# mainPower.net
KiCad netlist of a schematic drawn in Altium Designer
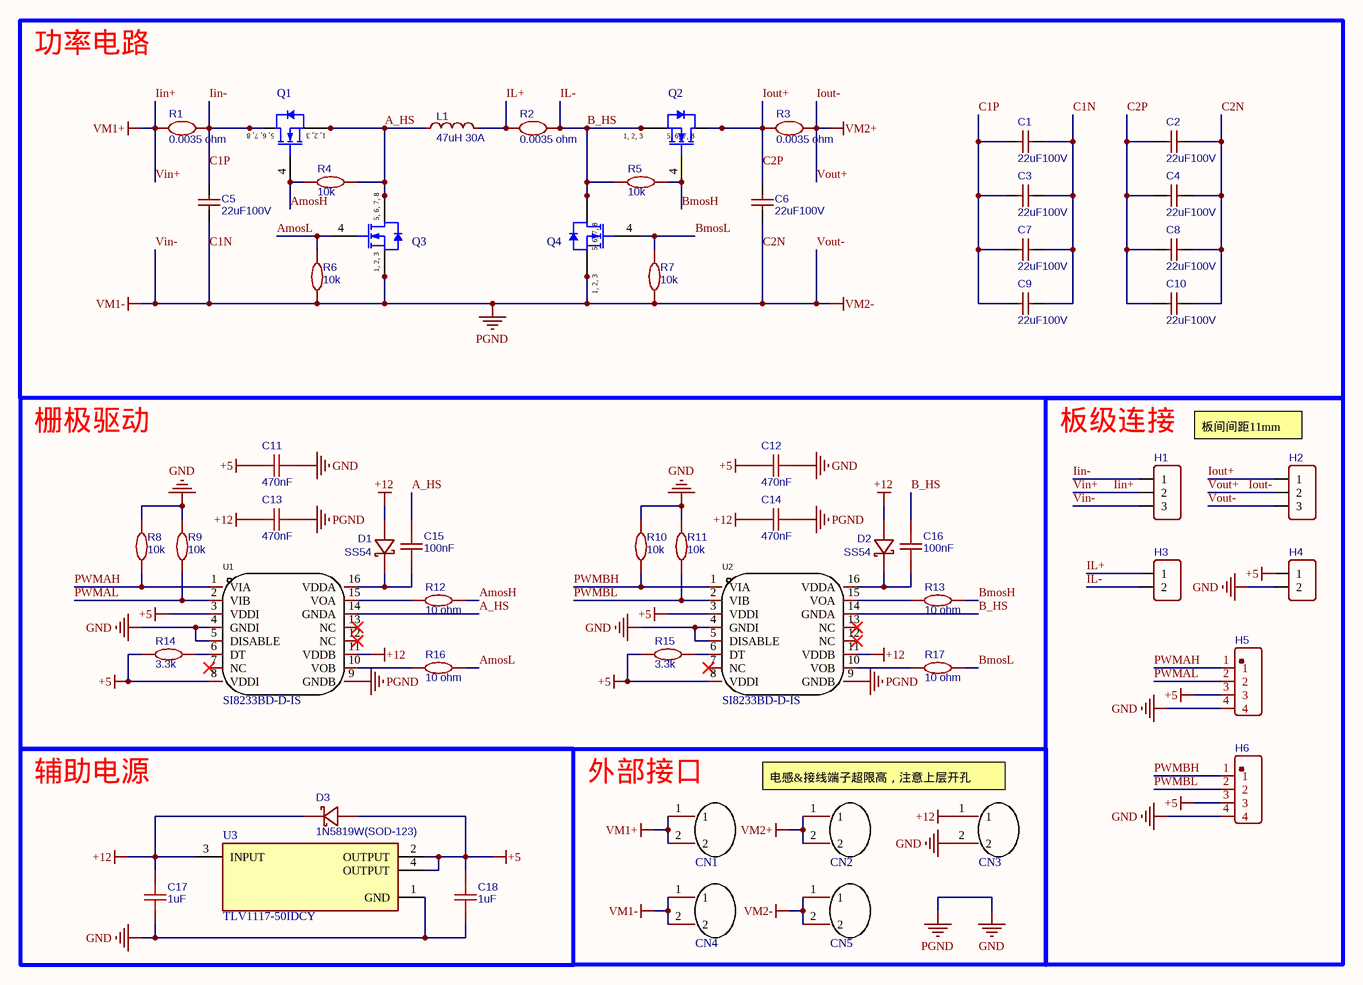
[diagram p0: mainPower.SchDoc]

(export (version "E")
  (design (tool "Eeschema 10.0.6"))
  (components
    (comp (ref "C1")
      (value "22uF100V")
      (footprint "C1206")
      (fields
        (field (name "BOM_MANUFACTURER PART") "1206B102K202NT")
        (field (name "BOM_SUPPLIER PART") "C9196")
      )
      (libsource (lib "RC_schlib") (part "C1206"))
    )
    (comp (ref "C2")
      (value "22uF100V")
      (footprint "C1206")
      (fields
        (field (name "BOM_MANUFACTURER PART") "1206B102K202NT")
        (field (name "BOM_SUPPLIER PART") "C9196")
      )
      (libsource (lib "RC_schlib") (part "C1206"))
    )
    (comp (ref "C3")
      (value "22uF100V")
      (footprint "C1206")
      (fields
        (field (name "BOM_MANUFACTURER PART") "1206B102K202NT")
        (field (name "BOM_SUPPLIER PART") "C9196")
      )
      (libsource (lib "RC_schlib") (part "C1206"))
    )
    (comp (ref "C4")
      (value "22uF100V")
      (footprint "C1206")
      (fields
        (field (name "BOM_MANUFACTURER PART") "1206B102K202NT")
        (field (name "BOM_SUPPLIER PART") "C9196")
      )
      (libsource (lib "RC_schlib") (part "C1206"))
    )
    (comp (ref "C5")
      (value "22uF100V")
      (footprint "C1206")
      (fields
        (field (name "BOM_MANUFACTURER PART") "1206B102K202NT")
        (field (name "BOM_SUPPLIER PART") "C9196")
      )
      (libsource (lib "RC_schlib") (part "C1206"))
    )
    (comp (ref "C6")
      (value "22uF100V")
      (footprint "C1206")
      (fields
        (field (name "BOM_MANUFACTURER PART") "1206B102K202NT")
        (field (name "BOM_SUPPLIER PART") "C9196")
      )
      (libsource (lib "RC_schlib") (part "C1206"))
    )
    (comp (ref "C7")
      (value "22uF100V")
      (footprint "C1206")
      (fields
        (field (name "BOM_MANUFACTURER PART") "1206B102K202NT")
        (field (name "BOM_SUPPLIER PART") "C9196")
      )
      (libsource (lib "RC_schlib") (part "C1206"))
    )
    (comp (ref "C8")
      (value "22uF100V")
      (footprint "C1206")
      (fields
        (field (name "BOM_MANUFACTURER PART") "1206B102K202NT")
        (field (name "BOM_SUPPLIER PART") "C9196")
      )
      (libsource (lib "RC_schlib") (part "C1206"))
    )
    (comp (ref "C9")
      (value "22uF100V")
      (footprint "C1206")
      (fields
        (field (name "BOM_MANUFACTURER PART") "1206B102K202NT")
        (field (name "BOM_SUPPLIER PART") "C9196")
      )
      (libsource (lib "RC_schlib") (part "C1206"))
    )
    (comp (ref "C10")
      (value "22uF100V")
      (footprint "C1206")
      (fields
        (field (name "BOM_MANUFACTURER PART") "1206B102K202NT")
        (field (name "BOM_SUPPLIER PART") "C9196")
      )
      (libsource (lib "RC_schlib") (part "C1206"))
    )
    (comp (ref "C11")
      (value "470nF")
      (footprint "C0603")
      (fields
        (field (name "BOM_MANUFACTURER PART") "CC0603KRX7R9BB104")
        (field (name "BOM_SUPPLIER PART") "C14663")
      )
      (libsource (lib "RC_schlib") (part "C0603"))
    )
    (comp (ref "C12")
      (value "470nF")
      (footprint "C0603")
      (fields
        (field (name "BOM_MANUFACTURER PART") "CC0603KRX7R9BB104")
        (field (name "BOM_SUPPLIER PART") "C14663")
      )
      (libsource (lib "RC_schlib") (part "C0603"))
    )
    (comp (ref "C13")
      (value "470nF")
      (footprint "C0603")
      (fields
        (field (name "BOM_MANUFACTURER PART") "CC0603KRX7R9BB104")
        (field (name "BOM_SUPPLIER PART") "C14663")
      )
      (libsource (lib "RC_schlib") (part "C0603"))
    )
    (comp (ref "C14")
      (value "470nF")
      (footprint "C0603")
      (fields
        (field (name "BOM_MANUFACTURER PART") "CC0603KRX7R9BB104")
        (field (name "BOM_SUPPLIER PART") "C14663")
      )
      (libsource (lib "RC_schlib") (part "C0603"))
    )
    (comp (ref "C15")
      (value "100nF")
      (footprint "C0603")
      (fields
        (field (name "BOM_MANUFACTURER PART") "CC0603KRX7R9BB104")
        (field (name "BOM_SUPPLIER PART") "C14663")
      )
      (libsource (lib "RC_schlib") (part "C0603"))
    )
    (comp (ref "C16")
      (value "100nF")
      (footprint "C0603")
      (fields
        (field (name "BOM_MANUFACTURER PART") "CC0603KRX7R9BB104")
        (field (name "BOM_SUPPLIER PART") "C14663")
      )
      (libsource (lib "RC_schlib") (part "C0603"))
    )
    (comp (ref "C17")
      (value "1uF")
      (footprint "C0603")
      (fields
        (field (name "BOM_MANUFACTURER PART") "CC0603KRX7R9BB104")
        (field (name "BOM_SUPPLIER PART") "C14663")
      )
      (libsource (lib "RC_schlib") (part "C0603"))
    )
    (comp (ref "C18")
      (value "1uF")
      (footprint "C0603")
      (fields
        (field (name "BOM_MANUFACTURER PART") "CC0603KRX7R9BB104")
        (field (name "BOM_SUPPLIER PART") "C14663")
      )
      (libsource (lib "RC_schlib") (part "C0603"))
    )
    (comp (ref "CN1")
      (value "1729128")
      (footprint "CONN-TH_2P-P5.08")
      (description "间距:5.08mm;排数:1;每排PIN数:2;安装方式:直针;额定电流:13.5A;额定电压:400V;工作温度范围:-;颜色:绿色;")
      (fields (field (name "MANUFACTURER") "Phoenix Contact(菲尼克斯)"))
      (libsource (lib "MKDSN") (part "MKDSN5.08-2P"))
    )
    (comp (ref "CN2")
      (value "1729128")
      (footprint "CONN-TH_2P-P5.08")
      (description "间距:5.08mm;排数:1;每排PIN数:2;安装方式:直针;额定电流:13.5A;额定电压:400V;工作温度范围:-;颜色:绿色;")
      (fields (field (name "MANUFACTURER") "Phoenix Contact(菲尼克斯)"))
      (libsource (lib "MKDSN") (part "MKDSN5.08-2P"))
    )
    (comp (ref "CN3")
      (value "1729128")
      (footprint "CONN-TH_2P-P5.08")
      (description "间距:5.08mm;排数:1;每排PIN数:2;安装方式:直针;额定电流:13.5A;额定电压:400V;工作温度范围:-;颜色:绿色;")
      (fields (field (name "MANUFACTURER") "Phoenix Contact(菲尼克斯)"))
      (libsource (lib "MKDSN") (part "MKDSN5.08-2P"))
    )
    (comp (ref "CN4")
      (value "1729128")
      (footprint "CONN-TH_2P-P5.08")
      (description "间距:5.08mm;排数:1;每排PIN数:2;安装方式:直针;额定电流:13.5A;额定电压:400V;工作温度范围:-;颜色:绿色;")
      (fields (field (name "MANUFACTURER") "Phoenix Contact(菲尼克斯)"))
      (libsource (lib "MKDSN") (part "MKDSN5.08-2P"))
    )
    (comp (ref "CN5")
      (value "1729128")
      (footprint "CONN-TH_2P-P5.08")
      (description "间距:5.08mm;排数:1;每排PIN数:2;安装方式:直针;额定电流:13.5A;额定电压:400V;工作温度范围:-;颜色:绿色;")
      (fields (field (name "MANUFACTURER") "Phoenix Contact(菲尼克斯)"))
      (libsource (lib "MKDSN") (part "MKDSN5.08-2P"))
    )
    (comp (ref "D1")
      (value "SS54")
      (footprint "SMA")
      (fields
        (field (name "BOM_SUPPLIER PART") "C2931787")
        (field (name "BOM_MANUFACTURER PART") "SS34")
        (field (name "CONTRIBUTOR") "LCSC")
      )
      (libsource (lib "Diode_schlib") (part "SS34(SMA)"))
    )
    (comp (ref "D2")
      (value "SS54")
      (footprint "SMA")
      (fields
        (field (name "BOM_SUPPLIER PART") "C2931787")
        (field (name "BOM_MANUFACTURER PART") "SS34")
        (field (name "CONTRIBUTOR") "LCSC")
      )
      (libsource (lib "Diode_schlib") (part "SS34(SMA)"))
    )
    (comp (ref "D3")
      (value "1N5819W(SOD-123)")
      (footprint "SOD-123")
      (fields
        (field (name "BOM_SUPPLIER PART") "C2931787")
        (field (name "BOM_MANUFACTURER PART") "SS34")
        (field (name "CONTRIBUTOR") "LCSC")
      )
      (libsource (lib "Diode_schlib") (part "1N5819W(SOD-123)"))
    )
    (comp (ref "H1")
      (value "Header-Male-2.54_1x3")
      (footprint "HDR2.54-LI-3P")
      (fields
        (field (name "BOM_MANUFACTURER PART") "Header2.54mm 1*3P")
        (field (name "BOM_SUPPLIER PART") "C49257")
      )
      (libsource (lib "2.54CN_schlib") (part "Header-Male-2.54_1x3"))
    )
    (comp (ref "H2")
      (value "Header-Male-2.54_1x3")
      (footprint "HDR2.54-LI-3P")
      (fields
        (field (name "BOM_MANUFACTURER PART") "Header2.54mm 1*3P")
        (field (name "BOM_SUPPLIER PART") "C49257")
      )
      (libsource (lib "2.54CN_schlib") (part "Header-Male-2.54_1x3"))
    )
    (comp (ref "H3")
      (value "Header-Male-2.54_1x2")
      (footprint "HDR2.54-LI-2P")
      (fields
        (field (name "BOM_MANUFACTURER PART") "Header2.54mm 1*3P")
        (field (name "BOM_SUPPLIER PART") "C49257")
      )
      (libsource (lib "2.54CN_schlib") (part "Header-Male-2.54_1x2"))
    )
    (comp (ref "H4")
      (value "Header-Male-2.54_1x2")
      (footprint "HDR2.54-LI-2P")
      (fields
        (field (name "BOM_MANUFACTURER PART") "Header2.54mm 1*3P")
        (field (name "BOM_SUPPLIER PART") "C49257")
      )
      (libsource (lib "2.54CN_schlib") (part "Header-Male-2.54_1x2"))
    )
    (comp (ref "H5")
      (value "Header-Male-2.54_1x4")
      (footprint "HDR2.54-LI-4P")
      (fields (field (name "BOM_SUPPLIER PART") "C247921") (field (name "CONTRIBUTOR") "LCSC"))
      (libsource (lib "2.54CN_schlib") (part "Header-Male-2.54_1x4"))
    )
    (comp (ref "H6")
      (value "Header-Male-2.54_1x4")
      (footprint "HDR2.54-LI-4P")
      (fields (field (name "BOM_SUPPLIER PART") "C247921") (field (name "CONTRIBUTOR") "LCSC"))
      (libsource (lib "2.54CN_schlib") (part "Header-Male-2.54_1x4"))
    )
    (comp (ref "L1")
      (value "47uH 30A")
      (footprint "106-125立式")
      (fields
        (field (name "BOM_SUPPLIER PART") "C2936653")
        (field (name "BOM_MANUFACTURER PART") "HA42-4R7MT")
        (field (name "CONTRIBUTOR") "LCSC")
      )
      (libsource (lib "Inductance_schlib") (part "106-125铁硅铝磁环电感"))
    )
    (comp (ref "Q1")
      (value "BSC070N10NS3 G")
      (footprint "INF-PG-TDSON-8-1_V")
      (fields
        (field (name "MANUFACTURER") "Infineon")
        (field (name "MANUFACTURER PART NUMBER") "BSC070N10NS3G")
      )
      (libsource (lib "MOSFET_schlib") (part "BSC070N10NS3G"))
    )
    (comp (ref "Q2")
      (value "BSC070N10NS3 G")
      (footprint "INF-PG-TDSON-8-1_V")
      (fields
        (field (name "MANUFACTURER") "Infineon")
        (field (name "MANUFACTURER PART NUMBER") "BSC070N10NS3G")
      )
      (libsource (lib "MOSFET_schlib") (part "BSC070N10NS3G"))
    )
    (comp (ref "Q3")
      (value "BSC070N10NS3 G")
      (footprint "INF-PG-TDSON-8-1_V")
      (fields
        (field (name "MANUFACTURER") "Infineon")
        (field (name "MANUFACTURER PART NUMBER") "BSC070N10NS3G")
      )
      (libsource (lib "MOSFET_schlib") (part "BSC070N10NS3G"))
    )
    (comp (ref "Q4")
      (value "BSC070N10NS3 G")
      (footprint "INF-PG-TDSON-8-1_V")
      (fields
        (field (name "MANUFACTURER") "Infineon")
        (field (name "MANUFACTURER PART NUMBER") "BSC070N10NS3G")
      )
      (libsource (lib "MOSFET_schlib") (part "BSC070N10NS3G"))
    )
    (comp (ref "R1")
      (value "0.0035 ohm")
      (footprint "R2512")
      (fields
        (field (name "BOM_SUPPLIER PART") "C375694")
        (field (name "BOM_MANUFACTURER PART") "SR2512FK-0751RL")
        (field (name "CONTRIBUTOR") "LCSC")
      )
      (libsource (lib "RC_schlib") (part "R2512"))
    )
    (comp (ref "R2")
      (value "0.0035 ohm")
      (footprint "R2512")
      (fields
        (field (name "BOM_SUPPLIER PART") "C375694")
        (field (name "BOM_MANUFACTURER PART") "SR2512FK-0751RL")
        (field (name "CONTRIBUTOR") "LCSC")
      )
      (libsource (lib "RC_schlib") (part "R2512"))
    )
    (comp (ref "R3")
      (value "0.0035 ohm")
      (footprint "R2512")
      (fields
        (field (name "BOM_SUPPLIER PART") "C375694")
        (field (name "BOM_MANUFACTURER PART") "SR2512FK-0751RL")
        (field (name "CONTRIBUTOR") "LCSC")
      )
      (libsource (lib "RC_schlib") (part "R2512"))
    )
    (comp (ref "R4")
      (value "10k")
      (footprint "R0603")
      (fields
        (field (name "BOM_SUPPLIER PART") "C326890")
        (field (name "BOM_MANUFACTURER PART") "SR0603JR-071RL")
        (field (name "CONTRIBUTOR") "LCSC")
      )
      (libsource (lib "RC_schlib") (part "R0603"))
    )
    (comp (ref "R5")
      (value "10k")
      (footprint "R0603")
      (fields
        (field (name "BOM_SUPPLIER PART") "C326890")
        (field (name "BOM_MANUFACTURER PART") "SR0603JR-071RL")
        (field (name "CONTRIBUTOR") "LCSC")
      )
      (libsource (lib "RC_schlib") (part "R0603"))
    )
    (comp (ref "R6")
      (value "10k")
      (footprint "R0603")
      (fields
        (field (name "BOM_SUPPLIER PART") "C326890")
        (field (name "BOM_MANUFACTURER PART") "SR0603JR-071RL")
        (field (name "CONTRIBUTOR") "LCSC")
      )
      (libsource (lib "RC_schlib") (part "R0603"))
    )
    (comp (ref "R7")
      (value "10k")
      (footprint "R0603")
      (fields
        (field (name "BOM_SUPPLIER PART") "C326890")
        (field (name "BOM_MANUFACTURER PART") "SR0603JR-071RL")
        (field (name "CONTRIBUTOR") "LCSC")
      )
      (libsource (lib "RC_schlib") (part "R0603"))
    )
    (comp (ref "R8")
      (value "10k")
      (footprint "R0603")
      (fields
        (field (name "BOM_SUPPLIER PART") "C326890")
        (field (name "BOM_MANUFACTURER PART") "SR0603JR-071RL")
        (field (name "CONTRIBUTOR") "LCSC")
      )
      (libsource (lib "RC_schlib") (part "R0603"))
    )
    (comp (ref "R9")
      (value "10k")
      (footprint "R0603")
      (fields
        (field (name "BOM_SUPPLIER PART") "C326890")
        (field (name "BOM_MANUFACTURER PART") "SR0603JR-071RL")
        (field (name "CONTRIBUTOR") "LCSC")
      )
      (libsource (lib "RC_schlib") (part "R0603"))
    )
    (comp (ref "R10")
      (value "10k")
      (footprint "R0603")
      (fields
        (field (name "BOM_SUPPLIER PART") "C326890")
        (field (name "BOM_MANUFACTURER PART") "SR0603JR-071RL")
        (field (name "CONTRIBUTOR") "LCSC")
      )
      (libsource (lib "RC_schlib") (part "R0603"))
    )
    (comp (ref "R11")
      (value "10k")
      (footprint "R0603")
      (fields
        (field (name "BOM_SUPPLIER PART") "C326890")
        (field (name "BOM_MANUFACTURER PART") "SR0603JR-071RL")
        (field (name "CONTRIBUTOR") "LCSC")
      )
      (libsource (lib "RC_schlib") (part "R0603"))
    )
    (comp (ref "R12")
      (value "10 ohm")
      (footprint "R0603")
      (fields
        (field (name "BOM_SUPPLIER PART") "C326890")
        (field (name "BOM_MANUFACTURER PART") "SR0603JR-071RL")
        (field (name "CONTRIBUTOR") "LCSC")
      )
      (libsource (lib "RC_schlib") (part "R0603"))
    )
    (comp (ref "R13")
      (value "10 ohm")
      (footprint "R0603")
      (fields
        (field (name "BOM_SUPPLIER PART") "C326890")
        (field (name "BOM_MANUFACTURER PART") "SR0603JR-071RL")
        (field (name "CONTRIBUTOR") "LCSC")
      )
      (libsource (lib "RC_schlib") (part "R0603"))
    )
    (comp (ref "R14")
      (value "3.3k")
      (footprint "R0603")
      (fields
        (field (name "BOM_SUPPLIER PART") "C326890")
        (field (name "BOM_MANUFACTURER PART") "SR0603JR-071RL")
        (field (name "CONTRIBUTOR") "LCSC")
      )
      (libsource (lib "RC_schlib") (part "R0603"))
    )
    (comp (ref "R15")
      (value "3.3k")
      (footprint "R0603")
      (fields
        (field (name "BOM_SUPPLIER PART") "C326890")
        (field (name "BOM_MANUFACTURER PART") "SR0603JR-071RL")
        (field (name "CONTRIBUTOR") "LCSC")
      )
      (libsource (lib "RC_schlib") (part "R0603"))
    )
    (comp (ref "R16")
      (value "10 ohm")
      (footprint "R0603")
      (fields
        (field (name "BOM_SUPPLIER PART") "C326890")
        (field (name "BOM_MANUFACTURER PART") "SR0603JR-071RL")
        (field (name "CONTRIBUTOR") "LCSC")
      )
      (libsource (lib "RC_schlib") (part "R0603"))
    )
    (comp (ref "R17")
      (value "10 ohm")
      (footprint "R0603")
      (fields
        (field (name "BOM_SUPPLIER PART") "C326890")
        (field (name "BOM_MANUFACTURER PART") "SR0603JR-071RL")
        (field (name "CONTRIBUTOR") "LCSC")
      )
      (libsource (lib "RC_schlib") (part "R0603"))
    )
    (comp (ref "U1")
      (value "SI8233BD-D-IS")
      (footprint "SOIC-16_L10.3-W7.5-P1.27-LS10.3-BL")
      (description "高速隔离半桥栅极驱动器")
      (fields (field (name "MANUFACTURER") "SILICON LABS(芯科)"))
      (libsource (lib "IC_schlib") (part "SI8233BD-D-IS"))
    )
    (comp (ref "U2")
      (value "SI8233BD-D-IS")
      (footprint "SOIC-16_L10.3-W7.5-P1.27-LS10.3-BL")
      (description "高速隔离半桥栅极驱动器")
      (fields (field (name "MANUFACTURER") "SILICON LABS(芯科)"))
      (libsource (lib "IC_schlib") (part "SI8233BD-D-IS"))
    )
    (comp (ref "U3")
      (value "TLV1117-50IDCY")
      (footprint "FP-DCY0004A-MFG")
      (description "IC REG LINEAR 5V 800MA SOT223-4")
      (libsource (lib "Altium Content Vault") (part "e308c0431133a401381f8e374ae96fd"))
    )
  )
  (nets
    (net (code "1") (name "+5") (class "Default")
      (node (ref "C11") (pin "2") (pinfunction "2_2") (pintype "passive"))
      (node (ref "C12") (pin "2") (pinfunction "2_2") (pintype "passive"))
      (node (ref "C18") (pin "2") (pinfunction "2_2") (pintype "passive"))
      (node (ref "D3") (pin "1") (pinfunction "A_1") (pintype "passive"))
      (node (ref "H4") (pin "1") (pinfunction "1_1") (pintype "passive"))
      (node (ref "H5") (pin "3") (pinfunction "3_3") (pintype "passive"))
      (node (ref "H6") (pin "3") (pinfunction "3_3") (pintype "passive"))
      (node (ref "R14") (pin "1") (pinfunction "1_1") (pintype "passive"))
      (node (ref "R15") (pin "1") (pinfunction "1_1") (pintype "passive"))
      (node (ref "U1") (pin "3") (pinfunction "VDDI_3") (pintype "passive"))
      (node (ref "U1") (pin "8") (pinfunction "VDDI_8") (pintype "passive"))
      (node (ref "U2") (pin "3") (pinfunction "VDDI_3") (pintype "passive"))
      (node (ref "U2") (pin "8") (pinfunction "VDDI_8") (pintype "passive"))
      (node (ref "U3") (pin "2") (pinfunction "OUTPUT_2") (pintype "power_in"))
      (node (ref "U3") (pin "4") (pinfunction "OUTPUT_4") (pintype "power_in"))
    )
    (net (code "2") (name "+12") (class "Default")
      (node (ref "C13") (pin "2") (pinfunction "2_2") (pintype "passive"))
      (node (ref "C14") (pin "2") (pinfunction "2_2") (pintype "passive"))
      (node (ref "C17") (pin "2") (pinfunction "2_2") (pintype "passive"))
      (node (ref "CN3") (pin "1") (pinfunction "1_1") (pintype "passive"))
      (node (ref "D1") (pin "1") (pinfunction "A_1") (pintype "passive"))
      (node (ref "D2") (pin "1") (pinfunction "A_1") (pintype "passive"))
      (node (ref "D3") (pin "2") (pinfunction "K_2") (pintype "passive"))
      (node (ref "U1") (pin "11") (pinfunction "VDDB_11") (pintype "passive"))
      (node (ref "U2") (pin "11") (pinfunction "VDDB_11") (pintype "passive"))
      (node (ref "U3") (pin "3") (pinfunction "INPUT_3") (pintype "power_in"))
    )
    (net (code "3") (name "/A_HS") (class "Default")
      (node (ref "C15") (pin "2") (pinfunction "2_2") (pintype "passive"))
      (node (ref "L1") (pin "1") (pinfunction "1_1") (pintype "passive"))
      (node (ref "Q1") (pin "1") (pinfunction "SOURCE_1") (pintype "passive"))
      (node (ref "Q1") (pin "2") (pinfunction "SOURCE_2") (pintype "passive"))
      (node (ref "Q1") (pin "3") (pinfunction "SOURCE_3") (pintype "passive"))
      (node (ref "Q3") (pin "5") (pinfunction "DRAIN_5") (pintype "passive"))
      (node (ref "Q3") (pin "6") (pinfunction "DRAIN_6") (pintype "passive"))
      (node (ref "Q3") (pin "7") (pinfunction "DRAIN_7") (pintype "passive"))
      (node (ref "Q3") (pin "8") (pinfunction "DRAIN_8") (pintype "passive"))
      (node (ref "R4") (pin "1") (pinfunction "1_1") (pintype "passive"))
      (node (ref "U1") (pin "14") (pinfunction "GNDA_14") (pintype "passive"))
    )
    (net (code "4") (name "/AmosH") (class "Default")
      (node (ref "Q1") (pin "4") (pinfunction "GATE_4") (pintype "passive"))
      (node (ref "R12") (pin "2") (pinfunction "2_2") (pintype "passive"))
      (node (ref "R4") (pin "2") (pinfunction "2_2") (pintype "passive"))
    )
    (net (code "5") (name "/AmosL") (class "Default")
      (node (ref "Q3") (pin "4") (pinfunction "GATE_4") (pintype "passive"))
      (node (ref "R16") (pin "2") (pinfunction "2_2") (pintype "passive"))
      (node (ref "R6") (pin "2") (pinfunction "2_2") (pintype "passive"))
    )
    (net (code "6") (name "/B_HS") (class "Default")
      (node (ref "C16") (pin "2") (pinfunction "2_2") (pintype "passive"))
      (node (ref "H3") (pin "2") (pinfunction "2_2") (pintype "passive"))
      (node (ref "Q2") (pin "1") (pinfunction "SOURCE_1") (pintype "passive"))
      (node (ref "Q2") (pin "2") (pinfunction "SOURCE_2") (pintype "passive"))
      (node (ref "Q2") (pin "3") (pinfunction "SOURCE_3") (pintype "passive"))
      (node (ref "Q4") (pin "5") (pinfunction "DRAIN_5") (pintype "passive"))
      (node (ref "Q4") (pin "6") (pinfunction "DRAIN_6") (pintype "passive"))
      (node (ref "Q4") (pin "7") (pinfunction "DRAIN_7") (pintype "passive"))
      (node (ref "Q4") (pin "8") (pinfunction "DRAIN_8") (pintype "passive"))
      (node (ref "R2") (pin "2") (pinfunction "2_2") (pintype "passive"))
      (node (ref "R5") (pin "2") (pinfunction "2_2") (pintype "passive"))
      (node (ref "U2") (pin "14") (pinfunction "GNDA_14") (pintype "passive"))
    )
    (net (code "7") (name "/BmosH") (class "Default")
      (node (ref "Q2") (pin "4") (pinfunction "GATE_4") (pintype "passive"))
      (node (ref "R13") (pin "2") (pinfunction "2_2") (pintype "passive"))
      (node (ref "R5") (pin "1") (pinfunction "1_1") (pintype "passive"))
    )
    (net (code "8") (name "/BmosL") (class "Default")
      (node (ref "Q4") (pin "4") (pinfunction "GATE_4") (pintype "passive"))
      (node (ref "R17") (pin "2") (pinfunction "2_2") (pintype "passive"))
      (node (ref "R7") (pin "2") (pinfunction "2_2") (pintype "passive"))
    )
    (net (code "9") (name "/C1P") (class "Default")
      (node (ref "C1") (pin "1") (pinfunction "1_1") (pintype "passive"))
      (node (ref "C3") (pin "1") (pinfunction "1_1") (pintype "passive"))
      (node (ref "C5") (pin "2") (pinfunction "2_2") (pintype "passive"))
      (node (ref "C7") (pin "1") (pinfunction "1_1") (pintype "passive"))
      (node (ref "C9") (pin "1") (pinfunction "1_1") (pintype "passive"))
      (node (ref "H1") (pin "1") (pinfunction "1_1") (pintype "passive"))
      (node (ref "Q1") (pin "5") (pinfunction "DRAIN_5") (pintype "passive"))
      (node (ref "Q1") (pin "6") (pinfunction "DRAIN_6") (pintype "passive"))
      (node (ref "Q1") (pin "7") (pinfunction "DRAIN_7") (pintype "passive"))
      (node (ref "Q1") (pin "8") (pinfunction "DRAIN_8") (pintype "passive"))
      (node (ref "R1") (pin "2") (pinfunction "2_2") (pintype "passive"))
    )
    (net (code "10") (name "/C2P") (class "Default")
      (node (ref "C10") (pin "1") (pinfunction "1_1") (pintype "passive"))
      (node (ref "C2") (pin "1") (pinfunction "1_1") (pintype "passive"))
      (node (ref "C4") (pin "1") (pinfunction "1_1") (pintype "passive"))
      (node (ref "C6") (pin "2") (pinfunction "2_2") (pintype "passive"))
      (node (ref "C8") (pin "1") (pinfunction "1_1") (pintype "passive"))
      (node (ref "H2") (pin "1") (pinfunction "1_1") (pintype "passive"))
      (node (ref "Q2") (pin "5") (pinfunction "DRAIN_5") (pintype "passive"))
      (node (ref "Q2") (pin "6") (pinfunction "DRAIN_6") (pintype "passive"))
      (node (ref "Q2") (pin "7") (pinfunction "DRAIN_7") (pintype "passive"))
      (node (ref "Q2") (pin "8") (pinfunction "DRAIN_8") (pintype "passive"))
      (node (ref "R3") (pin "1") (pinfunction "1_1") (pintype "passive"))
    )
    (net (code "11") (name "/IL+") (class "Default")
      (node (ref "H3") (pin "1") (pinfunction "1_1") (pintype "passive"))
      (node (ref "L1") (pin "2") (pinfunction "2_2") (pintype "passive"))
      (node (ref "R2") (pin "1") (pinfunction "1_1") (pintype "passive"))
    )
    (net (code "12") (name "/PWMAH") (class "Default")
      (node (ref "H5") (pin "1") (pinfunction "1_1") (pintype "passive"))
      (node (ref "R8") (pin "1") (pinfunction "1_1") (pintype "passive"))
      (node (ref "U1") (pin "1") (pinfunction "VIA_1") (pintype "passive"))
    )
    (net (code "13") (name "/PWMAL") (class "Default")
      (node (ref "H5") (pin "2") (pinfunction "2_2") (pintype "passive"))
      (node (ref "R9") (pin "1") (pinfunction "1_1") (pintype "passive"))
      (node (ref "U1") (pin "2") (pinfunction "VIB_2") (pintype "passive"))
    )
    (net (code "14") (name "/PWMBH") (class "Default")
      (node (ref "H6") (pin "1") (pinfunction "1_1") (pintype "passive"))
      (node (ref "R10") (pin "1") (pinfunction "1_1") (pintype "passive"))
      (node (ref "U2") (pin "1") (pinfunction "VIA_1") (pintype "passive"))
    )
    (net (code "15") (name "/PWMBL") (class "Default")
      (node (ref "H6") (pin "2") (pinfunction "2_2") (pintype "passive"))
      (node (ref "R11") (pin "1") (pinfunction "1_1") (pintype "passive"))
      (node (ref "U2") (pin "2") (pinfunction "VIB_2") (pintype "passive"))
    )
    (net (code "16") (name "GND") (class "Default")
      (node (ref "C1") (pin "2") (pinfunction "2_2") (pintype "passive"))
      (node (ref "C10") (pin "2") (pinfunction "2_2") (pintype "passive"))
      (node (ref "C11") (pin "1") (pinfunction "1_1") (pintype "passive"))
      (node (ref "C12") (pin "1") (pinfunction "1_1") (pintype "passive"))
      (node (ref "C13") (pin "1") (pinfunction "1_1") (pintype "passive"))
      (node (ref "C14") (pin "1") (pinfunction "1_1") (pintype "passive"))
      (node (ref "C17") (pin "1") (pinfunction "1_1") (pintype "passive"))
      (node (ref "C18") (pin "1") (pinfunction "1_1") (pintype "passive"))
      (node (ref "C2") (pin "2") (pinfunction "2_2") (pintype "passive"))
      (node (ref "C3") (pin "2") (pinfunction "2_2") (pintype "passive"))
      (node (ref "C4") (pin "2") (pinfunction "2_2") (pintype "passive"))
      (node (ref "C5") (pin "1") (pinfunction "1_1") (pintype "passive"))
      (node (ref "C6") (pin "1") (pinfunction "1_1") (pintype "passive"))
      (node (ref "C7") (pin "2") (pinfunction "2_2") (pintype "passive"))
      (node (ref "C8") (pin "2") (pinfunction "2_2") (pintype "passive"))
      (node (ref "C9") (pin "2") (pinfunction "2_2") (pintype "passive"))
      (node (ref "CN3") (pin "2") (pinfunction "2_2") (pintype "passive"))
      (node (ref "CN4") (pin "1") (pinfunction "1_1") (pintype "passive"))
      (node (ref "CN4") (pin "2") (pinfunction "2_2") (pintype "passive"))
      (node (ref "CN5") (pin "1") (pinfunction "1_1") (pintype "passive"))
      (node (ref "CN5") (pin "2") (pinfunction "2_2") (pintype "passive"))
      (node (ref "H1") (pin "3") (pinfunction "3_3") (pintype "passive"))
      (node (ref "H2") (pin "3") (pinfunction "3_3") (pintype "passive"))
      (node (ref "H4") (pin "2") (pinfunction "2_2") (pintype "passive"))
      (node (ref "H5") (pin "4") (pinfunction "4_4") (pintype "passive"))
      (node (ref "H6") (pin "4") (pinfunction "4_4") (pintype "passive"))
      (node (ref "Q3") (pin "1") (pinfunction "SOURCE_1") (pintype "passive"))
      (node (ref "Q3") (pin "2") (pinfunction "SOURCE_2") (pintype "passive"))
      (node (ref "Q3") (pin "3") (pinfunction "SOURCE_3") (pintype "passive"))
      (node (ref "Q4") (pin "1") (pinfunction "SOURCE_1") (pintype "passive"))
      (node (ref "Q4") (pin "2") (pinfunction "SOURCE_2") (pintype "passive"))
      (node (ref "Q4") (pin "3") (pinfunction "SOURCE_3") (pintype "passive"))
      (node (ref "R10") (pin "2") (pinfunction "2_2") (pintype "passive"))
      (node (ref "R11") (pin "2") (pinfunction "2_2") (pintype "passive"))
      (node (ref "R6") (pin "1") (pinfunction "1_1") (pintype "passive"))
      (node (ref "R7") (pin "1") (pinfunction "1_1") (pintype "passive"))
      (node (ref "R8") (pin "2") (pinfunction "2_2") (pintype "passive"))
      (node (ref "R9") (pin "2") (pinfunction "2_2") (pintype "passive"))
      (node (ref "U1") (pin "4") (pinfunction "GNDI_4") (pintype "passive"))
      (node (ref "U1") (pin "5") (pinfunction "DISABLE_5") (pintype "passive"))
      (node (ref "U1") (pin "9") (pinfunction "GNDB_9") (pintype "passive"))
      (node (ref "U2") (pin "4") (pinfunction "GNDI_4") (pintype "passive"))
      (node (ref "U2") (pin "5") (pinfunction "DISABLE_5") (pintype "passive"))
      (node (ref "U2") (pin "9") (pinfunction "GNDB_9") (pintype "passive"))
      (node (ref "U3") (pin "1") (pinfunction "GND_1") (pintype "power_in"))
    )
    (net (code "17") (name "Net-(D1-K)") (class "Default")
      (node (ref "C15") (pin "1") (pinfunction "1_1") (pintype "passive"))
      (node (ref "D1") (pin "2") (pinfunction "K_2") (pintype "passive"))
      (node (ref "U1") (pin "16") (pinfunction "VDDA_16") (pintype "passive"))
    )
    (net (code "18") (name "Net-(D2-K)") (class "Default")
      (node (ref "C16") (pin "1") (pinfunction "1_1") (pintype "passive"))
      (node (ref "D2") (pin "2") (pinfunction "K_2") (pintype "passive"))
      (node (ref "U2") (pin "16") (pinfunction "VDDA_16") (pintype "passive"))
    )
    (net (code "19") (name "Net-(U1-DT)") (class "Default")
      (node (ref "R14") (pin "2") (pinfunction "2_2") (pintype "passive"))
      (node (ref "U1") (pin "6") (pinfunction "DT_6") (pintype "passive"))
    )
    (net (code "20") (name "Net-(U1-VOA)") (class "Default")
      (node (ref "R12") (pin "1") (pinfunction "1_1") (pintype "passive"))
      (node (ref "U1") (pin "15") (pinfunction "VOA_15") (pintype "passive"))
    )
    (net (code "21") (name "Net-(U1-VOB)") (class "Default")
      (node (ref "R16") (pin "1") (pinfunction "1_1") (pintype "passive"))
      (node (ref "U1") (pin "10") (pinfunction "VOB_10") (pintype "passive"))
    )
    (net (code "22") (name "Net-(U2-DT)") (class "Default")
      (node (ref "R15") (pin "2") (pinfunction "2_2") (pintype "passive"))
      (node (ref "U2") (pin "6") (pinfunction "DT_6") (pintype "passive"))
    )
    (net (code "23") (name "Net-(U2-VOA)") (class "Default")
      (node (ref "R13") (pin "1") (pinfunction "1_1") (pintype "passive"))
      (node (ref "U2") (pin "15") (pinfunction "VOA_15") (pintype "passive"))
    )
    (net (code "24") (name "Net-(U2-VOB)") (class "Default")
      (node (ref "R17") (pin "1") (pinfunction "1_1") (pintype "passive"))
      (node (ref "U2") (pin "10") (pinfunction "VOB_10") (pintype "passive"))
    )
    (net (code "25") (name "VM1+") (class "Default")
      (node (ref "CN1") (pin "1") (pinfunction "1_1") (pintype "passive"))
      (node (ref "CN1") (pin "2") (pinfunction "2_2") (pintype "passive"))
      (node (ref "H1") (pin "2") (pinfunction "2_2") (pintype "passive"))
      (node (ref "R1") (pin "1") (pinfunction "1_1") (pintype "passive"))
    )
    (net (code "26") (name "VM2+") (class "Default")
      (node (ref "CN2") (pin "1") (pinfunction "1_1") (pintype "passive"))
      (node (ref "CN2") (pin "2") (pinfunction "2_2") (pintype "passive"))
      (node (ref "H2") (pin "2") (pinfunction "2_2") (pintype "passive"))
      (node (ref "R3") (pin "2") (pinfunction "2_2") (pintype "passive"))
    )
    (net (code "27") (name "unconnected-(U1-NC-Pad7)") (class "Default")
      (node (ref "U1") (pin "7") (pinfunction "NC_7") (pintype "passive+no_connect"))
    )
    (net (code "28") (name "unconnected-(U1-NC-Pad12)") (class "Default")
      (node (ref "U1") (pin "12") (pinfunction "NC_12") (pintype "passive+no_connect"))
    )
    (net (code "29") (name "unconnected-(U1-NC-Pad13)") (class "Default")
      (node (ref "U1") (pin "13") (pinfunction "NC_13") (pintype "passive+no_connect"))
    )
    (net (code "30") (name "unconnected-(U2-NC-Pad7)") (class "Default")
      (node (ref "U2") (pin "7") (pinfunction "NC_7") (pintype "passive+no_connect"))
    )
    (net (code "31") (name "unconnected-(U2-NC-Pad12)") (class "Default")
      (node (ref "U2") (pin "12") (pinfunction "NC_12") (pintype "passive+no_connect"))
    )
    (net (code "32") (name "unconnected-(U2-NC-Pad13)") (class "Default")
      (node (ref "U2") (pin "13") (pinfunction "NC_13") (pintype "passive+no_connect"))
    )
  )
)
